# Motor_Ctl.net
KiCad netlist of a schematic drawn in Altium Designer
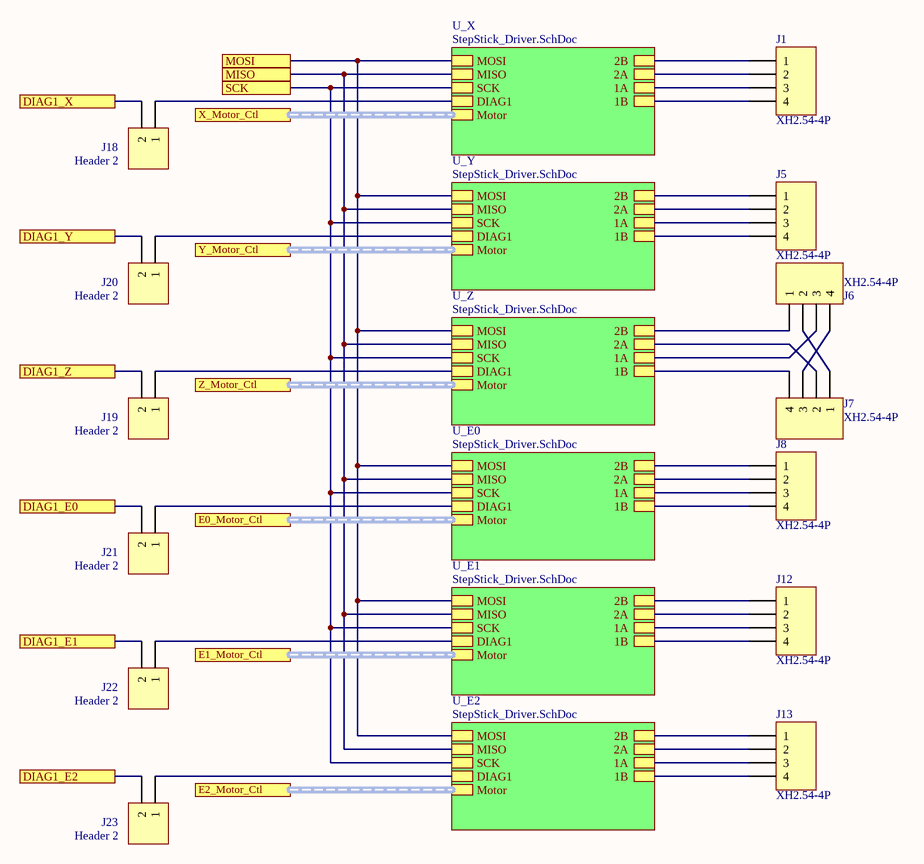
[diagram p0: Motor_Ctl.SchDoc]

(export (version "E")
  (design (tool "Eeschema 10.0.6"))
  (components
    (comp (ref "J1")
      (value "XH2.54-4P")
      (footprint "1x4 MTE Straight Header 2.54mm")
      (description "Header, 4-Pin")
      (fields (field (name "PUBLISHER") "Altium Limited"))
      (libsource (lib "Miscellaneous Connectors") (part "Header 4"))
    )
    (comp (ref "J5")
      (value "XH2.54-4P")
      (footprint "1x4 MTE Straight Header 2.54mm")
      (description "Header, 4-Pin")
      (fields (field (name "PUBLISHER") "Altium Limited"))
      (libsource (lib "Miscellaneous Connectors") (part "Header 4"))
    )
    (comp (ref "J6")
      (value "XH2.54-4P")
      (footprint "1x4 MTE Straight Header 2.54mm")
      (description "Header, 4-Pin")
      (fields (field (name "PUBLISHER") "Altium Limited"))
      (libsource (lib "") (part "Header 4_2"))
    )
    (comp (ref "J7")
      (value "XH2.54-4P")
      (footprint "1x4 MTE Straight Header 2.54mm")
      (description "Header, 4-Pin")
      (fields (field (name "PUBLISHER") "Altium Limited"))
      (libsource (lib "") (part "Header 4_1"))
    )
    (comp (ref "J8")
      (value "XH2.54-4P")
      (footprint "1x4 MTE Straight Header 2.54mm")
      (description "Header, 4-Pin")
      (fields (field (name "PUBLISHER") "Altium Limited"))
      (libsource (lib "Miscellaneous Connectors") (part "Header 4"))
    )
    (comp (ref "J12")
      (value "XH2.54-4P")
      (footprint "1x4 MTE Straight Header 2.54mm")
      (description "Header, 4-Pin")
      (fields (field (name "PUBLISHER") "Altium Limited"))
      (libsource (lib "Miscellaneous Connectors") (part "Header 4"))
    )
    (comp (ref "J13")
      (value "XH2.54-4P")
      (footprint "1x4 MTE Straight Header 2.54mm")
      (description "Header, 4-Pin")
      (fields (field (name "PUBLISHER") "Altium Limited"))
      (libsource (lib "Miscellaneous Connectors") (part "Header 4"))
    )
    (comp (ref "J18")
      (value "Header 2")
      (footprint "HDR1X2")
      (description "Header, 2-Pin")
      (fields (field (name "PUBLISHER") "Altium Limited"))
      (libsource (lib "Miscellaneous Connectors") (part "Header 2"))
    )
    (comp (ref "J19")
      (value "Header 2")
      (footprint "HDR1X2")
      (description "Header, 2-Pin")
      (fields (field (name "PUBLISHER") "Altium Limited"))
      (libsource (lib "Miscellaneous Connectors") (part "Header 2"))
    )
    (comp (ref "J20")
      (value "Header 2")
      (footprint "HDR1X2")
      (description "Header, 2-Pin")
      (fields (field (name "PUBLISHER") "Altium Limited"))
      (libsource (lib "Miscellaneous Connectors") (part "Header 2"))
    )
    (comp (ref "J21")
      (value "Header 2")
      (footprint "HDR1X2")
      (description "Header, 2-Pin")
      (fields (field (name "PUBLISHER") "Altium Limited"))
      (libsource (lib "Miscellaneous Connectors") (part "Header 2"))
    )
    (comp (ref "J22")
      (value "Header 2")
      (footprint "HDR1X2")
      (description "Header, 2-Pin")
      (fields (field (name "PUBLISHER") "Altium Limited"))
      (libsource (lib "Miscellaneous Connectors") (part "Header 2"))
    )
    (comp (ref "J23")
      (value "Header 2")
      (footprint "HDR1X2")
      (description "Header, 2-Pin")
      (fields (field (name "PUBLISHER") "Altium Limited"))
      (libsource (lib "Miscellaneous Connectors") (part "Header 2"))
    )
  )
  (nets
    (net (code "7") (name "/1A") (class "Default")
      (node (ref "J12") (pin "3") (pinfunction "3_3") (pintype "passive"))
    )
    (net (code "8") (name "/1A_1") (class "Default")
      (node (ref "J1") (pin "3") (pinfunction "3_3") (pintype "passive"))
    )
    (net (code "9") (name "/1A_2") (class "Default")
      (node (ref "J5") (pin "3") (pinfunction "3_3") (pintype "passive"))
    )
    (net (code "10") (name "/1A_3") (class "Default")
      (node (ref "J6") (pin "3") (pinfunction "3_3") (pintype "passive"))
    )
    (net (code "11") (name "/1A_4") (class "Default")
      (node (ref "J8") (pin "3") (pinfunction "3_3") (pintype "passive"))
    )
    (net (code "12") (name "/1A_5") (class "Default")
      (node (ref "J13") (pin "3") (pinfunction "3_3") (pintype "passive"))
    )
    (net (code "13") (name "/1B") (class "Default")
      (node (ref "J13") (pin "4") (pinfunction "4_4") (pintype "passive"))
    )
    (net (code "14") (name "/1B_1") (class "Default")
      (node (ref "J1") (pin "4") (pinfunction "4_4") (pintype "passive"))
    )
    (net (code "15") (name "/1B_2") (class "Default")
      (node (ref "J5") (pin "4") (pinfunction "4_4") (pintype "passive"))
    )
    (net (code "16") (name "/1B_3") (class "Default")
      (node (ref "J7") (pin "4") (pinfunction "4_4") (pintype "passive"))
    )
    (net (code "17") (name "/1B_4") (class "Default")
      (node (ref "J8") (pin "4") (pinfunction "4_4") (pintype "passive"))
    )
    (net (code "18") (name "/1B_5") (class "Default")
      (node (ref "J12") (pin "4") (pinfunction "4_4") (pintype "passive"))
    )
    (net (code "19") (name "/2A") (class "Default")
      (node (ref "J12") (pin "2") (pinfunction "2_2") (pintype "passive"))
    )
    (net (code "20") (name "/2A_1") (class "Default")
      (node (ref "J1") (pin "2") (pinfunction "2_2") (pintype "passive"))
    )
    (net (code "21") (name "/2A_2") (class "Default")
      (node (ref "J5") (pin "2") (pinfunction "2_2") (pintype "passive"))
    )
    (net (code "22") (name "/2A_3") (class "Default")
      (node (ref "J7") (pin "2") (pinfunction "2_2") (pintype "passive"))
    )
    (net (code "23") (name "/2A_4") (class "Default")
      (node (ref "J8") (pin "2") (pinfunction "2_2") (pintype "passive"))
    )
    (net (code "24") (name "/2A_5") (class "Default")
      (node (ref "J13") (pin "2") (pinfunction "2_2") (pintype "passive"))
    )
    (net (code "25") (name "/2B") (class "Default")
      (node (ref "J12") (pin "1") (pinfunction "1_1") (pintype "passive"))
    )
    (net (code "26") (name "/2B_1") (class "Default")
      (node (ref "J1") (pin "1") (pinfunction "1_1") (pintype "passive"))
    )
    (net (code "27") (name "/2B_2") (class "Default")
      (node (ref "J5") (pin "1") (pinfunction "1_1") (pintype "passive"))
    )
    (net (code "28") (name "/2B_3") (class "Default")
      (node (ref "J6") (pin "1") (pinfunction "1_1") (pintype "passive"))
    )
    (net (code "29") (name "/2B_4") (class "Default")
      (node (ref "J8") (pin "1") (pinfunction "1_1") (pintype "passive"))
    )
    (net (code "30") (name "/2B_5") (class "Default")
      (node (ref "J13") (pin "1") (pinfunction "1_1") (pintype "passive"))
    )
    (net (code "31") (name "/DIAG1") (class "Default")
      (node (ref "J23") (pin "1") (pinfunction "1_1") (pintype "passive"))
    )
    (net (code "32") (name "/DIAG1_1") (class "Default")
      (node (ref "J18") (pin "1") (pinfunction "1_1") (pintype "passive"))
    )
    (net (code "33") (name "/DIAG1_2") (class "Default")
      (node (ref "J20") (pin "1") (pinfunction "1_1") (pintype "passive"))
    )
    (net (code "34") (name "/DIAG1_3") (class "Default")
      (node (ref "J19") (pin "1") (pinfunction "1_1") (pintype "passive"))
    )
    (net (code "35") (name "/DIAG1_4") (class "Default")
      (node (ref "J22") (pin "1") (pinfunction "1_1") (pintype "passive"))
    )
    (net (code "36") (name "/DIAG1_5") (class "Default")
      (node (ref "J21") (pin "1") (pinfunction "1_1") (pintype "passive"))
    )
    (net (code "37") (name "/DIAG1_E0") (class "Default")
      (node (ref "J21") (pin "2") (pinfunction "2_2") (pintype "passive"))
    )
    (net (code "38") (name "/DIAG1_E1") (class "Default")
      (node (ref "J22") (pin "2") (pinfunction "2_2") (pintype "passive"))
    )
    (net (code "39") (name "/DIAG1_E2") (class "Default")
      (node (ref "J23") (pin "2") (pinfunction "2_2") (pintype "passive"))
    )
    (net (code "40") (name "/DIAG1_X") (class "Default")
      (node (ref "J18") (pin "2") (pinfunction "2_2") (pintype "passive"))
    )
    (net (code "41") (name "/DIAG1_Y") (class "Default")
      (node (ref "J20") (pin "2") (pinfunction "2_2") (pintype "passive"))
    )
    (net (code "42") (name "/DIAG1_Z") (class "Default")
      (node (ref "J19") (pin "2") (pinfunction "2_2") (pintype "passive"))
    )
    (net (code "52") (name "Net-(J6-Pad2)") (class "Default")
      (node (ref "J6") (pin "2") (pinfunction "2_2") (pintype "passive"))
      (node (ref "J7") (pin "1") (pinfunction "1_1") (pintype "passive"))
    )
    (net (code "53") (name "Net-(J6-Pad4)") (class "Default")
      (node (ref "J6") (pin "4") (pinfunction "4_4") (pintype "passive"))
      (node (ref "J7") (pin "3") (pinfunction "3_3") (pintype "passive"))
    )
  )
)
